# Schematic.net
KiCad netlist of a schematic drawn in EasyEDA
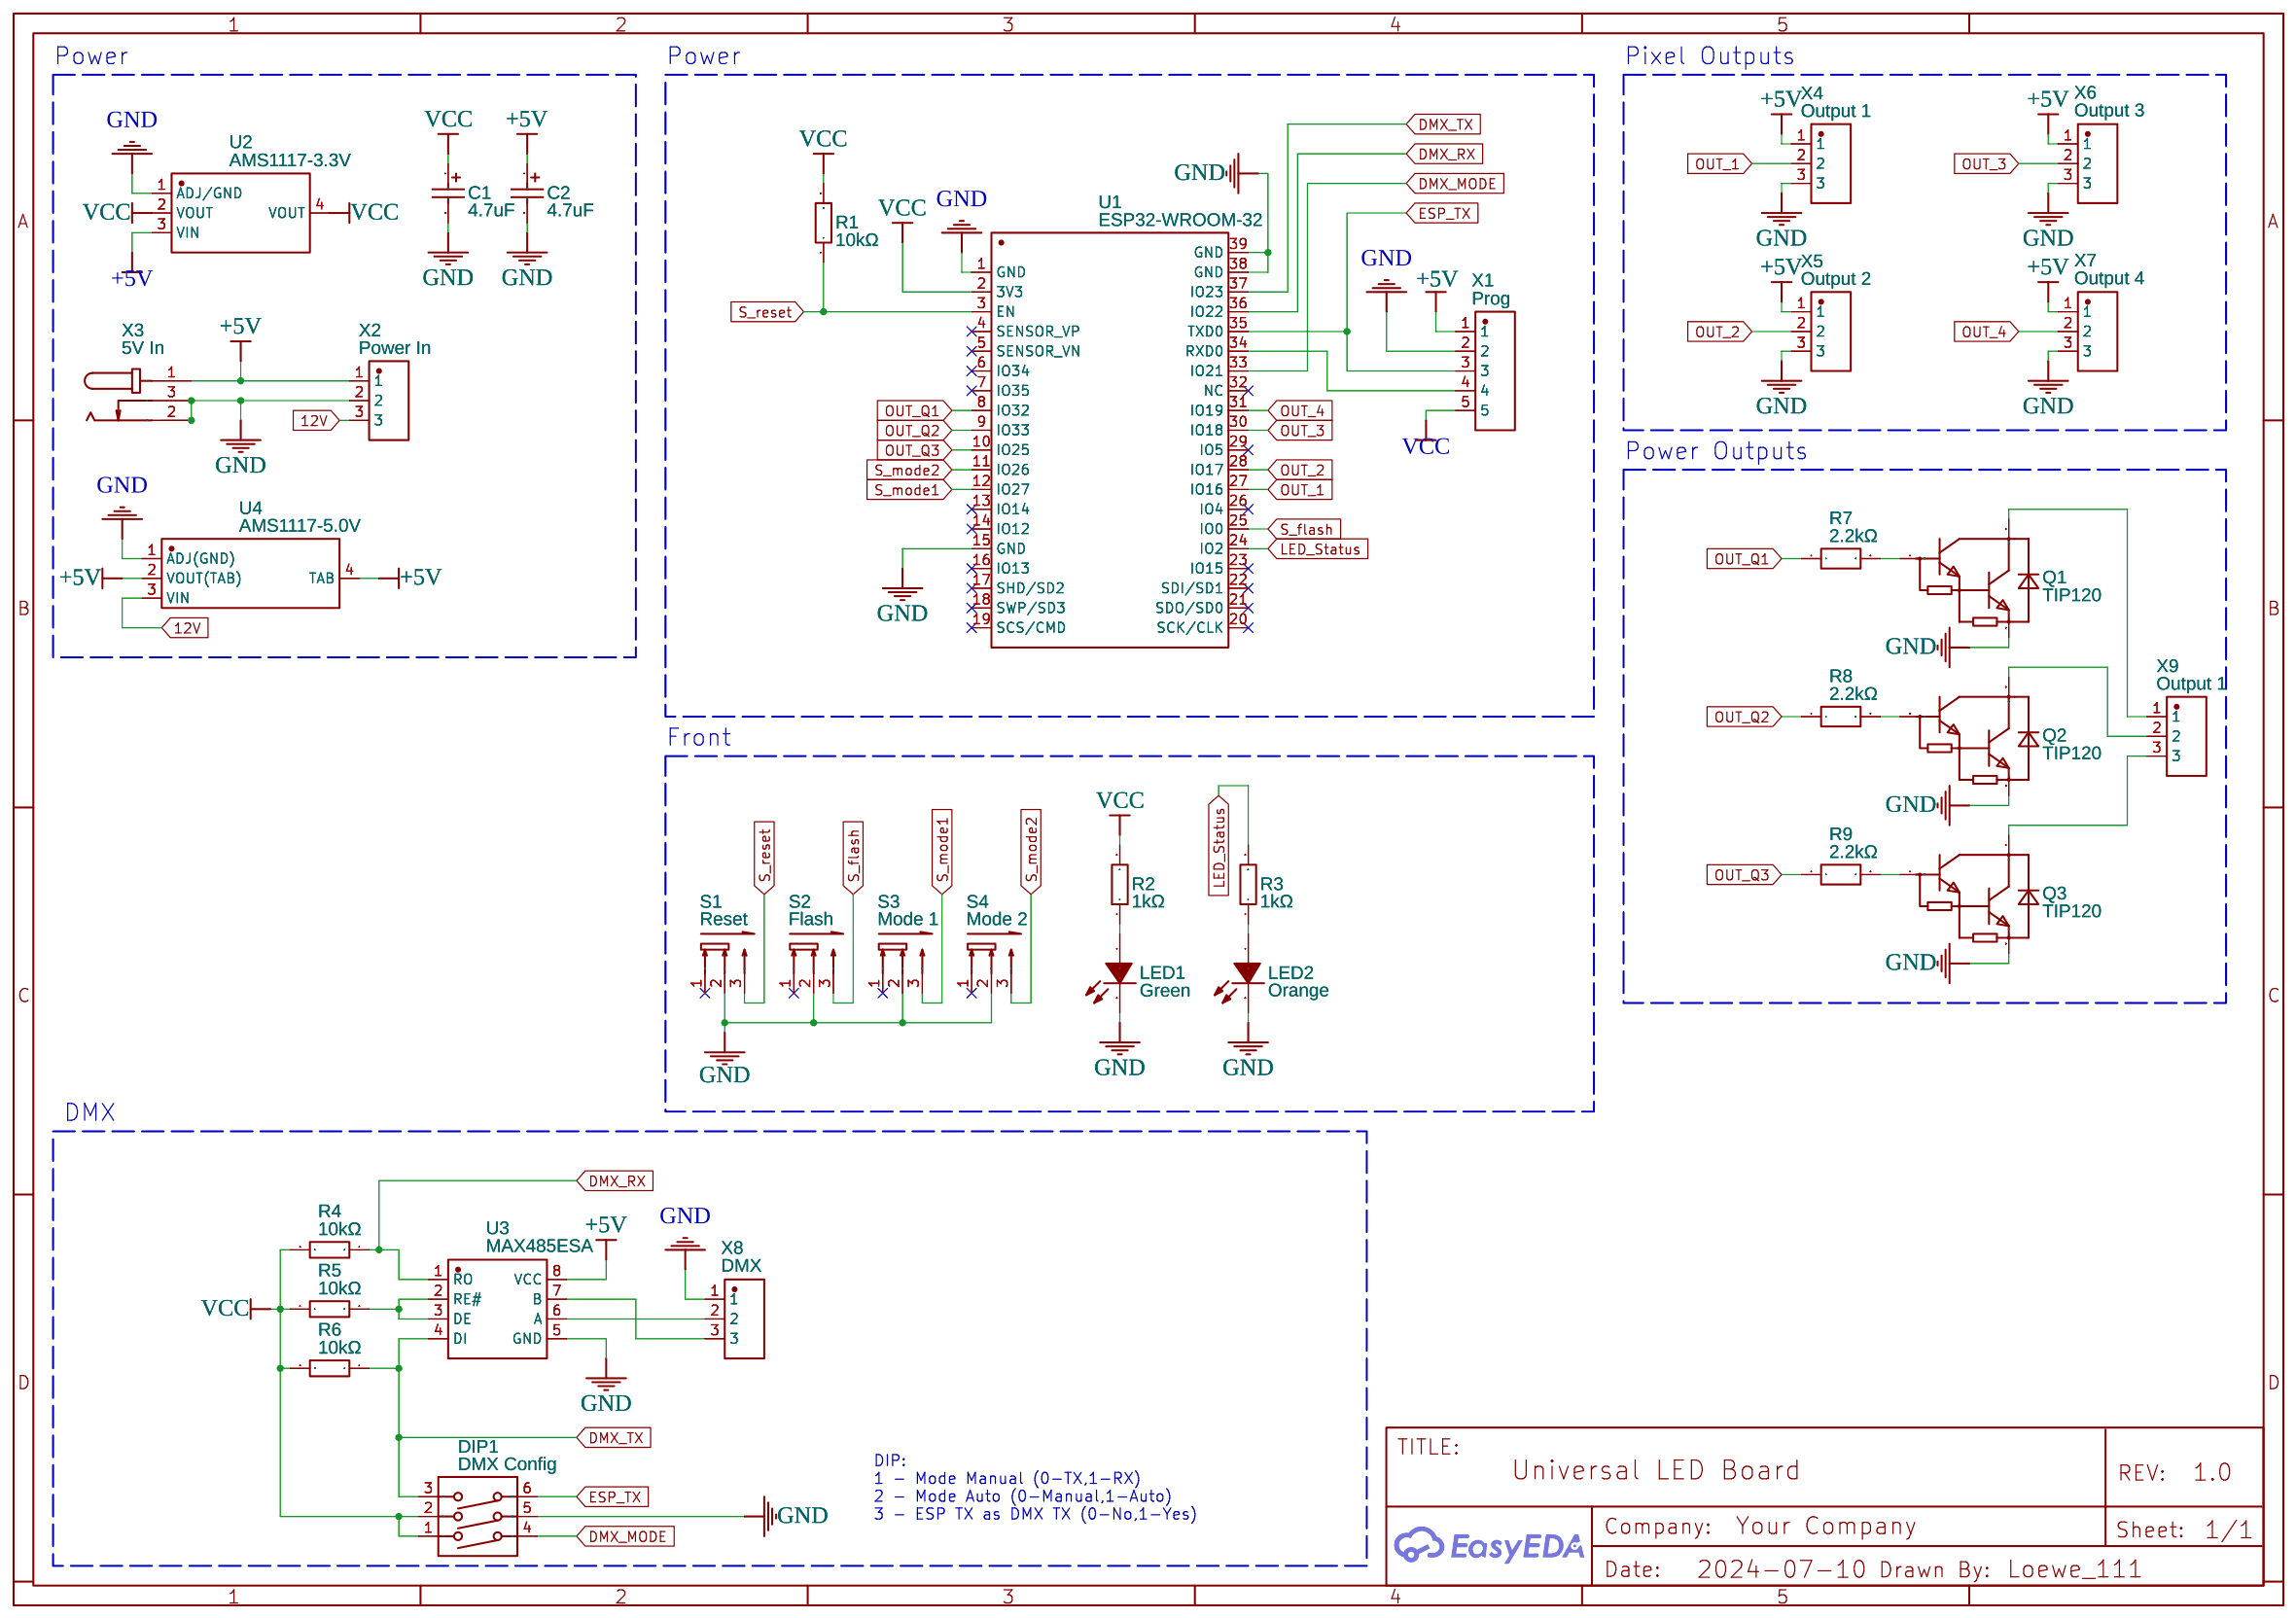
[diagram p0: schematic sheet]

(export (version "E")
  (design (tool "Eeschema 10.0.6"))
  (components
    (comp (ref "C1")
      (value "4.7uF")
      (fields
        (field (name "Manufacturer Part") "CA45-A-16V-4.7uF-K")
        (field (name "Manufacturer") "CEC(振华新云)")
      )
      (libsource (lib "") (part "CA45-A-16V-4.7UF-K"))
    )
    (comp (ref "C2")
      (value "4.7uF")
      (fields
        (field (name "Manufacturer Part") "CA45-A-16V-4.7uF-K")
        (field (name "Manufacturer") "CEC(振华新云)")
      )
      (libsource (lib "") (part "CA45-A-16V-4.7UF-K"))
    )
    (comp (ref "DIP1")
      (value "DMX Config")
      (fields (field (name "Manufacturer Part") "DSWB03LHGET") (field (name "Manufacturer") "YE"))
      (libsource (lib "") (part "DSWB03LHGET"))
    )
    (comp (ref "LED1")
      (value "Green")
      (fields (field (name "Manufacturer Part") "SZYY0603G") (field (name "Manufacturer") "yongyu(永裕光电)"))
      (libsource (lib "") (part "SZYY0603G"))
    )
    (comp (ref "LED2")
      (value "Orange")
      (fields (field (name "Manufacturer Part") "SZYY0603O") (field (name "Manufacturer") "yongyu(永裕光电)"))
      (libsource (lib "") (part "SZYY0603O"))
    )
    (comp (ref "Q1")
      (value "TIP120")
      (fields (field (name "Manufacturer") "ST(意法半导体)"))
      (libsource (lib "") (part "TIP120"))
    )
    (comp (ref "Q2")
      (value "TIP120")
      (fields (field (name "Manufacturer") "ST(意法半导体)"))
      (libsource (lib "") (part "TIP120"))
    )
    (comp (ref "Q3")
      (value "TIP120")
      (fields (field (name "Manufacturer") "ST(意法半导体)"))
      (libsource (lib "") (part "TIP120"))
    )
    (comp (ref "R1")
      (value "10kΩ")
      (fields
        (field (name "Manufacturer Part") "0603WAF1002T5E")
        (field (name "Manufacturer") "UNI-ROYAL(厚声)")
      )
      (libsource (lib "") (part "0603WAF1002T5E_2"))
    )
    (comp (ref "R2")
      (value "1kΩ")
      (fields (field (name "Manufacturer Part") "RC0603FR-071KL") (field (name "Manufacturer") "YAGEO(国巨)"))
      (libsource (lib "") (part "RC0603FR-071KL"))
    )
    (comp (ref "R3")
      (value "1kΩ")
      (fields (field (name "Manufacturer Part") "RC0603FR-071KL") (field (name "Manufacturer") "YAGEO(国巨)"))
      (libsource (lib "") (part "RC0603FR-071KL"))
    )
    (comp (ref "R4")
      (value "10kΩ")
      (fields
        (field (name "Manufacturer Part") "0603WAF1002T5E")
        (field (name "Manufacturer") "UNI-ROYAL(厚声)")
      )
      (libsource (lib "") (part "0603WAF1002T5E"))
    )
    (comp (ref "R5")
      (value "10kΩ")
      (fields
        (field (name "Manufacturer Part") "0603WAF1002T5E")
        (field (name "Manufacturer") "UNI-ROYAL(厚声)")
      )
      (libsource (lib "") (part "0603WAF1002T5E_1"))
    )
    (comp (ref "R6")
      (value "10kΩ")
      (fields
        (field (name "Manufacturer Part") "0603WAF1002T5E")
        (field (name "Manufacturer") "UNI-ROYAL(厚声)")
      )
      (libsource (lib "") (part "0603WAF1002T5E"))
    )
    (comp (ref "R7")
      (value "2.2kΩ")
      (fields (field (name "Manufacturer Part") "FRC0603J222 TS") (field (name "Manufacturer") "FOJAN(富捷)"))
      (libsource (lib "") (part "FRC0603J222 TS"))
    )
    (comp (ref "R8")
      (value "2.2kΩ")
      (fields (field (name "Manufacturer Part") "FRC0603J222 TS") (field (name "Manufacturer") "FOJAN(富捷)"))
      (libsource (lib "") (part "FRC0603J222 TS"))
    )
    (comp (ref "R9")
      (value "2.2kΩ")
      (fields (field (name "Manufacturer Part") "FRC0603J222 TS") (field (name "Manufacturer") "FOJAN(富捷)"))
      (libsource (lib "") (part "FRC0603J222 TS"))
    )
    (comp (ref "S1")
      (value "Reset")
      (fields
        (field (name "Manufacturer Part") "XKB5858-W-C")
        (field (name "Manufacturer") "XKB Connection(中国星坤)")
      )
      (libsource (lib "") (part "XKB5858-W-C"))
    )
    (comp (ref "S2")
      (value "Flash")
      (fields
        (field (name "Manufacturer Part") "XKB5858-W-C")
        (field (name "Manufacturer") "XKB Connection(中国星坤)")
      )
      (libsource (lib "") (part "XKB5858-W-C"))
    )
    (comp (ref "S3")
      (value "Mode 1")
      (fields
        (field (name "Manufacturer Part") "XKB5858-W-C")
        (field (name "Manufacturer") "XKB Connection(中国星坤)")
      )
      (libsource (lib "") (part "XKB5858-W-C"))
    )
    (comp (ref "S4")
      (value "Mode 2")
      (fields
        (field (name "Manufacturer Part") "XKB5858-W-C")
        (field (name "Manufacturer") "XKB Connection(中国星坤)")
      )
      (libsource (lib "") (part "XKB5858-W-C"))
    )
    (comp (ref "U1")
      (value "ESP32-WROOM-32")
      (fields
        (field (name "Manufacturer Part") "ESP32-WROOM-32-N4")
        (field (name "Manufacturer") "ESPRESSIF(乐鑫)")
      )
      (libsource (lib "") (part "ESP32-WROOM-32"))
    )
    (comp (ref "U2")
      (value "AMS1117-3.3V")
      (fields (field (name "Manufacturer") "WPMtek(维攀)"))
      (libsource (lib "") (part "AMS1117-3.3V"))
    )
    (comp (ref "U3")
      (value "MAX485ESA")
      (fields (field (name "Manufacturer Part") "max485ESA") (field (name "Manufacturer") "JSMSEMI(杰盛微)"))
      (libsource (lib "") (part "MAX485ESA"))
    )
    (comp (ref "U4")
      (value "AMS1117-5.0V")
      (fields (field (name "Manufacturer Part") "AMS1117-5.0") (field (name "Manufacturer") "UMW(友台半导体)"))
      (libsource (lib "") (part "AMS1117-5.0_C347223"))
    )
    (comp (ref "X1")
      (value "Prog")
      (fields
        (field (name "Manufacturer Part") "ZX-XH2.54-5PZZ")
        (field (name "Manufacturer") "Megastar(兆星)")
      )
      (libsource (lib "") (part "ZX-XH2.54-5PZZ"))
    )
    (comp (ref "X2")
      (value "Power In")
      (fields
        (field (name "Manufacturer Part") "DB128L-5.08-3P-GN-S")
        (field (name "Manufacturer") "DORABO(地博电气)")
      )
      (libsource (lib "") (part "DB128L-5.08-3P"))
    )
    (comp (ref "X3")
      (value "5V In")
      (fields (field (name "Manufacturer Part") "DC-005-A200") (field (name "Manufacturer") "XUNPU(讯普)"))
      (libsource (lib "") (part "DC-005-A200"))
    )
    (comp (ref "X4")
      (value "Output 1")
      (fields
        (field (name "Manufacturer Part") "DB128L-5.08-3P-GN-S")
        (field (name "Manufacturer") "DORABO(地博电气)")
      )
      (libsource (lib "") (part "DB128L-5.08-3P"))
    )
    (comp (ref "X5")
      (value "Output 2")
      (fields
        (field (name "Manufacturer Part") "DB128L-5.08-3P-GN-S")
        (field (name "Manufacturer") "DORABO(地博电气)")
      )
      (libsource (lib "") (part "DB128L-5.08-3P"))
    )
    (comp (ref "X6")
      (value "Output 3")
      (fields
        (field (name "Manufacturer Part") "ZX-XH2.54-3PZZ")
        (field (name "Manufacturer") "Megastar(兆星)")
      )
      (libsource (lib "") (part "ZX-XH2.54-3PZZ"))
    )
    (comp (ref "X7")
      (value "Output 4")
      (fields
        (field (name "Manufacturer Part") "ZX-XH2.54-3PZZ")
        (field (name "Manufacturer") "Megastar(兆星)")
      )
      (libsource (lib "") (part "ZX-XH2.54-3PZZ"))
    )
    (comp (ref "X8")
      (value "DMX")
      (fields
        (field (name "Manufacturer Part") "ZX-XH2.54-3PZZ")
        (field (name "Manufacturer") "Megastar(兆星)")
      )
      (libsource (lib "") (part "ZX-XH2.54-3PZZ"))
    )
    (comp (ref "X9")
      (value "Output 1")
      (fields
        (field (name "Manufacturer Part") "DB128L-5.08-3P-GN-S")
        (field (name "Manufacturer") "DORABO(地博电气)")
      )
      (libsource (lib "") (part "DB128L-5.08-3P"))
    )
  )
  (nets
    (net (code "1") (name "+5V") (class "Default")
      (node (ref "C2") (pin "1") (pinfunction "1_1") (pintype "input"))
      (node (ref "U2") (pin "3") (pinfunction "VIN_3") (pintype "unspecified"))
      (node (ref "U3") (pin "8") (pinfunction "VCC_8") (pintype "unspecified"))
      (node (ref "U4") (pin "2") (pinfunction "VOUT(TAB)_2") (pintype "unspecified"))
      (node (ref "U4") (pin "4") (pinfunction "TAB_4") (pintype "unspecified"))
      (node (ref "X1") (pin "1") (pinfunction "1_1") (pintype "unspecified"))
      (node (ref "X2") (pin "1") (pinfunction "1_1") (pintype "unspecified"))
      (node (ref "X3") (pin "1") (pinfunction "1_1") (pintype "unspecified"))
      (node (ref "X4") (pin "1") (pinfunction "1_1") (pintype "unspecified"))
      (node (ref "X5") (pin "1") (pinfunction "1_1") (pintype "unspecified"))
      (node (ref "X6") (pin "1") (pinfunction "1_1") (pintype "unspecified"))
      (node (ref "X7") (pin "1") (pinfunction "1_1") (pintype "unspecified"))
    )
    (net (code "2") (name "12V") (class "Default")
      (node (ref "U4") (pin "3") (pinfunction "VIN_3") (pintype "unspecified"))
      (node (ref "X2") (pin "3") (pinfunction "3_3") (pintype "unspecified"))
    )
    (net (code "3") (name "DMX_MODE") (class "Default")
      (node (ref "DIP1") (pin "4") (pinfunction "4_4") (pintype "unspecified"))
      (node (ref "U1") (pin "33") (pinfunction "IO21_33") (pintype "unspecified"))
    )
    (net (code "4") (name "DMX_RX") (class "Default")
      (node (ref "R4") (pin "1") (pinfunction "1_1") (pintype "input"))
      (node (ref "U1") (pin "36") (pinfunction "IO22_36") (pintype "unspecified"))
      (node (ref "U3") (pin "1") (pinfunction "RO_1") (pintype "unspecified"))
    )
    (net (code "5") (name "DMX_TX") (class "Default")
      (node (ref "DIP1") (pin "3") (pinfunction "3_3") (pintype "unspecified"))
      (node (ref "R6") (pin "1") (pinfunction "1_1") (pintype "input"))
      (node (ref "U1") (pin "37") (pinfunction "IO23_37") (pintype "unspecified"))
      (node (ref "U3") (pin "4") (pinfunction "DI_4") (pintype "unspecified"))
    )
    (net (code "6") (name "ESP_TX") (class "Default")
      (node (ref "DIP1") (pin "6") (pinfunction "6_6") (pintype "unspecified"))
      (node (ref "U1") (pin "35") (pinfunction "TXD0_35") (pintype "unspecified"))
      (node (ref "X1") (pin "3") (pinfunction "3_3") (pintype "unspecified"))
    )
    (net (code "7") (name "GND") (class "Default")
      (node (ref "C1") (pin "2") (pinfunction "2_2") (pintype "input"))
      (node (ref "C2") (pin "2") (pinfunction "2_2") (pintype "input"))
      (node (ref "DIP1") (pin "5") (pinfunction "5_5") (pintype "unspecified"))
      (node (ref "LED1") (pin "2") (pinfunction "-_2") (pintype "unspecified"))
      (node (ref "LED2") (pin "2") (pinfunction "-_2") (pintype "unspecified"))
      (node (ref "Q1") (pin "3") (pinfunction "E_3") (pintype "input"))
      (node (ref "Q2") (pin "3") (pinfunction "E_3") (pintype "input"))
      (node (ref "Q3") (pin "3") (pinfunction "E_3") (pintype "input"))
      (node (ref "S1") (pin "2") (pinfunction "2_2") (pintype "unspecified"))
      (node (ref "S2") (pin "2") (pinfunction "2_2") (pintype "unspecified"))
      (node (ref "S3") (pin "2") (pinfunction "2_2") (pintype "unspecified"))
      (node (ref "S4") (pin "2") (pinfunction "2_2") (pintype "unspecified"))
      (node (ref "U1") (pin "1") (pinfunction "GND_1") (pintype "unspecified"))
      (node (ref "U1") (pin "15") (pinfunction "GND_15") (pintype "unspecified"))
      (node (ref "U1") (pin "38") (pinfunction "GND_38") (pintype "unspecified"))
      (node (ref "U1") (pin "39") (pinfunction "GND_39") (pintype "unspecified"))
      (node (ref "U2") (pin "1") (pinfunction "ADJ/GND_1") (pintype "unspecified"))
      (node (ref "U3") (pin "5") (pinfunction "GND_5") (pintype "unspecified"))
      (node (ref "U4") (pin "1") (pinfunction "ADJ(GND)_1") (pintype "unspecified"))
      (node (ref "X1") (pin "2") (pinfunction "2_2") (pintype "unspecified"))
      (node (ref "X2") (pin "2") (pinfunction "2_2") (pintype "unspecified"))
      (node (ref "X3") (pin "2") (pinfunction "2_2") (pintype "unspecified"))
      (node (ref "X3") (pin "3") (pinfunction "3_3") (pintype "unspecified"))
      (node (ref "X4") (pin "3") (pinfunction "3_3") (pintype "unspecified"))
      (node (ref "X5") (pin "3") (pinfunction "3_3") (pintype "unspecified"))
      (node (ref "X6") (pin "3") (pinfunction "3_3") (pintype "unspecified"))
      (node (ref "X7") (pin "3") (pinfunction "3_3") (pintype "unspecified"))
      (node (ref "X8") (pin "1") (pinfunction "1_1") (pintype "unspecified"))
    )
    (net (code "8") (name "LED_Status") (class "Default")
      (node (ref "R3") (pin "2") (pinfunction "2_2") (pintype "input"))
      (node (ref "U1") (pin "24") (pinfunction "IO2_24") (pintype "unspecified"))
    )
    (net (code "9") (name "Net-(LED1-+)") (class "Default")
      (node (ref "LED1") (pin "1") (pinfunction "+_1") (pintype "unspecified"))
      (node (ref "R2") (pin "1") (pinfunction "1_1") (pintype "input"))
    )
    (net (code "10") (name "Net-(LED2-+)") (class "Default")
      (node (ref "LED2") (pin "1") (pinfunction "+_1") (pintype "unspecified"))
      (node (ref "R3") (pin "1") (pinfunction "1_1") (pintype "input"))
    )
    (net (code "11") (name "Net-(Q1-B)") (class "Default")
      (node (ref "Q1") (pin "1") (pinfunction "B_1") (pintype "input"))
      (node (ref "R7") (pin "2") (pinfunction "2_2") (pintype "unspecified"))
    )
    (net (code "12") (name "Net-(Q1-C)") (class "Default")
      (node (ref "Q1") (pin "2") (pinfunction "C_2") (pintype "input"))
      (node (ref "X9") (pin "1") (pinfunction "1_1") (pintype "unspecified"))
    )
    (net (code "13") (name "Net-(Q2-B)") (class "Default")
      (node (ref "Q2") (pin "1") (pinfunction "B_1") (pintype "input"))
      (node (ref "R8") (pin "2") (pinfunction "2_2") (pintype "unspecified"))
    )
    (net (code "14") (name "Net-(Q2-C)") (class "Default")
      (node (ref "Q2") (pin "2") (pinfunction "C_2") (pintype "input"))
      (node (ref "X9") (pin "2") (pinfunction "2_2") (pintype "unspecified"))
    )
    (net (code "15") (name "Net-(Q3-B)") (class "Default")
      (node (ref "Q3") (pin "1") (pinfunction "B_1") (pintype "input"))
      (node (ref "R9") (pin "2") (pinfunction "2_2") (pintype "unspecified"))
    )
    (net (code "16") (name "Net-(Q3-C)") (class "Default")
      (node (ref "Q3") (pin "2") (pinfunction "C_2") (pintype "input"))
      (node (ref "X9") (pin "3") (pinfunction "3_3") (pintype "unspecified"))
    )
    (net (code "17") (name "Net-(U1-RXD0)") (class "Default")
      (node (ref "U1") (pin "34") (pinfunction "RXD0_34") (pintype "unspecified"))
      (node (ref "X1") (pin "4") (pinfunction "4_4") (pintype "unspecified"))
    )
    (net (code "18") (name "Net-(U3-A)") (class "Default")
      (node (ref "U3") (pin "6") (pinfunction "A_6") (pintype "unspecified"))
      (node (ref "X8") (pin "2") (pinfunction "2_2") (pintype "unspecified"))
    )
    (net (code "19") (name "Net-(U3-B)") (class "Default")
      (node (ref "U3") (pin "7") (pinfunction "B_7") (pintype "unspecified"))
      (node (ref "X8") (pin "3") (pinfunction "3_3") (pintype "unspecified"))
    )
    (net (code "20") (name "Net-(U3-DE)") (class "Default")
      (node (ref "R5") (pin "2") (pinfunction "2_2") (pintype "input"))
      (node (ref "U3") (pin "2") (pinfunction "RE#_2") (pintype "unspecified"))
      (node (ref "U3") (pin "3") (pinfunction "DE_3") (pintype "unspecified"))
    )
    (net (code "21") (name "OUT_1") (class "Default")
      (node (ref "U1") (pin "27") (pinfunction "IO16_27") (pintype "unspecified"))
      (node (ref "X4") (pin "2") (pinfunction "2_2") (pintype "unspecified"))
    )
    (net (code "22") (name "OUT_2") (class "Default")
      (node (ref "U1") (pin "28") (pinfunction "IO17_28") (pintype "unspecified"))
      (node (ref "X5") (pin "2") (pinfunction "2_2") (pintype "unspecified"))
    )
    (net (code "23") (name "OUT_3") (class "Default")
      (node (ref "U1") (pin "30") (pinfunction "IO18_30") (pintype "unspecified"))
      (node (ref "X6") (pin "2") (pinfunction "2_2") (pintype "unspecified"))
    )
    (net (code "24") (name "OUT_4") (class "Default")
      (node (ref "U1") (pin "31") (pinfunction "IO19_31") (pintype "unspecified"))
      (node (ref "X7") (pin "2") (pinfunction "2_2") (pintype "unspecified"))
    )
    (net (code "25") (name "OUT_Q1") (class "Default")
      (node (ref "R7") (pin "1") (pinfunction "1_1") (pintype "unspecified"))
      (node (ref "U1") (pin "8") (pinfunction "IO32_8") (pintype "unspecified"))
    )
    (net (code "26") (name "OUT_Q2") (class "Default")
      (node (ref "R8") (pin "1") (pinfunction "1_1") (pintype "unspecified"))
      (node (ref "U1") (pin "9") (pinfunction "IO33_9") (pintype "unspecified"))
    )
    (net (code "27") (name "OUT_Q3") (class "Default")
      (node (ref "R9") (pin "1") (pinfunction "1_1") (pintype "unspecified"))
      (node (ref "U1") (pin "10") (pinfunction "IO25_10") (pintype "unspecified"))
    )
    (net (code "28") (name "S_flash") (class "Default")
      (node (ref "S2") (pin "3") (pinfunction "3_3") (pintype "unspecified"))
      (node (ref "U1") (pin "25") (pinfunction "IO0_25") (pintype "unspecified"))
    )
    (net (code "29") (name "S_mode1") (class "Default")
      (node (ref "S3") (pin "3") (pinfunction "3_3") (pintype "unspecified"))
      (node (ref "U1") (pin "12") (pinfunction "IO27_12") (pintype "unspecified"))
    )
    (net (code "30") (name "S_mode2") (class "Default")
      (node (ref "S4") (pin "3") (pinfunction "3_3") (pintype "unspecified"))
      (node (ref "U1") (pin "11") (pinfunction "IO26_11") (pintype "unspecified"))
    )
    (net (code "31") (name "S_reset") (class "Default")
      (node (ref "R1") (pin "1") (pinfunction "1_1") (pintype "input"))
      (node (ref "S1") (pin "3") (pinfunction "3_3") (pintype "unspecified"))
      (node (ref "U1") (pin "3") (pinfunction "EN_3") (pintype "unspecified"))
    )
    (net (code "32") (name "VCC") (class "Default")
      (node (ref "C1") (pin "1") (pinfunction "1_1") (pintype "input"))
      (node (ref "DIP1") (pin "1") (pinfunction "1_1") (pintype "unspecified"))
      (node (ref "DIP1") (pin "2") (pinfunction "2_2") (pintype "unspecified"))
      (node (ref "R1") (pin "2") (pinfunction "2_2") (pintype "input"))
      (node (ref "R2") (pin "2") (pinfunction "2_2") (pintype "input"))
      (node (ref "R4") (pin "2") (pinfunction "2_2") (pintype "input"))
      (node (ref "R5") (pin "1") (pinfunction "1_1") (pintype "input"))
      (node (ref "R6") (pin "2") (pinfunction "2_2") (pintype "input"))
      (node (ref "U1") (pin "2") (pinfunction "3V3_2") (pintype "unspecified"))
      (node (ref "U2") (pin "2") (pinfunction "VOUT_2") (pintype "unspecified"))
      (node (ref "U2") (pin "4") (pinfunction "VOUT_4") (pintype "unspecified"))
      (node (ref "X1") (pin "5") (pinfunction "5_5") (pintype "unspecified"))
    )
    (net (code "33") (name "unconnected-(S1-Pad1)") (class "Default")
      (node (ref "S1") (pin "1") (pinfunction "1_1") (pintype "unspecified+no_connect"))
    )
    (net (code "34") (name "unconnected-(S2-Pad1)") (class "Default")
      (node (ref "S2") (pin "1") (pinfunction "1_1") (pintype "unspecified+no_connect"))
    )
    (net (code "35") (name "unconnected-(S3-Pad1)") (class "Default")
      (node (ref "S3") (pin "1") (pinfunction "1_1") (pintype "unspecified+no_connect"))
    )
    (net (code "36") (name "unconnected-(S4-Pad1)") (class "Default")
      (node (ref "S4") (pin "1") (pinfunction "1_1") (pintype "unspecified+no_connect"))
    )
    (net (code "37") (name "unconnected-(U1-IO4-Pad26)") (class "Default")
      (node (ref "U1") (pin "26") (pinfunction "IO4_26") (pintype "unspecified+no_connect"))
    )
    (net (code "38") (name "unconnected-(U1-IO5-Pad29)") (class "Default")
      (node (ref "U1") (pin "29") (pinfunction "IO5_29") (pintype "unspecified+no_connect"))
    )
    (net (code "39") (name "unconnected-(U1-IO12-Pad14)") (class "Default")
      (node (ref "U1") (pin "14") (pinfunction "IO12_14") (pintype "unspecified+no_connect"))
    )
    (net (code "40") (name "unconnected-(U1-IO13-Pad16)") (class "Default")
      (node (ref "U1") (pin "16") (pinfunction "IO13_16") (pintype "unspecified+no_connect"))
    )
    (net (code "41") (name "unconnected-(U1-IO14-Pad13)") (class "Default")
      (node (ref "U1") (pin "13") (pinfunction "IO14_13") (pintype "unspecified+no_connect"))
    )
    (net (code "42") (name "unconnected-(U1-IO15-Pad23)") (class "Default")
      (node (ref "U1") (pin "23") (pinfunction "IO15_23") (pintype "unspecified+no_connect"))
    )
    (net (code "43") (name "unconnected-(U1-IO34-Pad6)") (class "Default")
      (node (ref "U1") (pin "6") (pinfunction "IO34_6") (pintype "unspecified+no_connect"))
    )
    (net (code "44") (name "unconnected-(U1-IO35-Pad7)") (class "Default")
      (node (ref "U1") (pin "7") (pinfunction "IO35_7") (pintype "unspecified+no_connect"))
    )
    (net (code "45") (name "unconnected-(U1-NC-Pad32)") (class "Default")
      (node (ref "U1") (pin "32") (pinfunction "NC_32") (pintype "unspecified+no_connect"))
    )
    (net (code "46") (name "unconnected-(U1-SCK{slash}CLK-Pad20)") (class "Default")
      (node (ref "U1") (pin "20") (pinfunction "SCK/CLK_20") (pintype "unspecified+no_connect"))
    )
    (net (code "47") (name "unconnected-(U1-SCS{slash}CMD-Pad19)") (class "Default")
      (node (ref "U1") (pin "19") (pinfunction "SCS/CMD_19") (pintype "unspecified+no_connect"))
    )
    (net (code "48") (name "unconnected-(U1-SDI{slash}SD1-Pad22)") (class "Default")
      (node (ref "U1") (pin "22") (pinfunction "SDI/SD1_22") (pintype "unspecified+no_connect"))
    )
    (net (code "49") (name "unconnected-(U1-SDO{slash}SD0-Pad21)") (class "Default")
      (node (ref "U1") (pin "21") (pinfunction "SDO/SD0_21") (pintype "unspecified+no_connect"))
    )
    (net (code "50") (name "unconnected-(U1-SENSOR_VN-Pad5)") (class "Default")
      (node (ref "U1") (pin "5") (pinfunction "SENSOR_VN_5") (pintype "unspecified+no_connect"))
    )
    (net (code "51") (name "unconnected-(U1-SENSOR_VP-Pad4)") (class "Default")
      (node (ref "U1") (pin "4") (pinfunction "SENSOR_VP_4") (pintype "unspecified+no_connect"))
    )
    (net (code "52") (name "unconnected-(U1-SHD{slash}SD2-Pad17)") (class "Default")
      (node (ref "U1") (pin "17") (pinfunction "SHD/SD2_17") (pintype "unspecified+no_connect"))
    )
    (net (code "53") (name "unconnected-(U1-SWP{slash}SD3-Pad18)") (class "Default")
      (node (ref "U1") (pin "18") (pinfunction "SWP/SD3_18") (pintype "unspecified+no_connect"))
    )
  )
)
